# design.net
KiCad netlist of a schematic drawn in Altium Designer
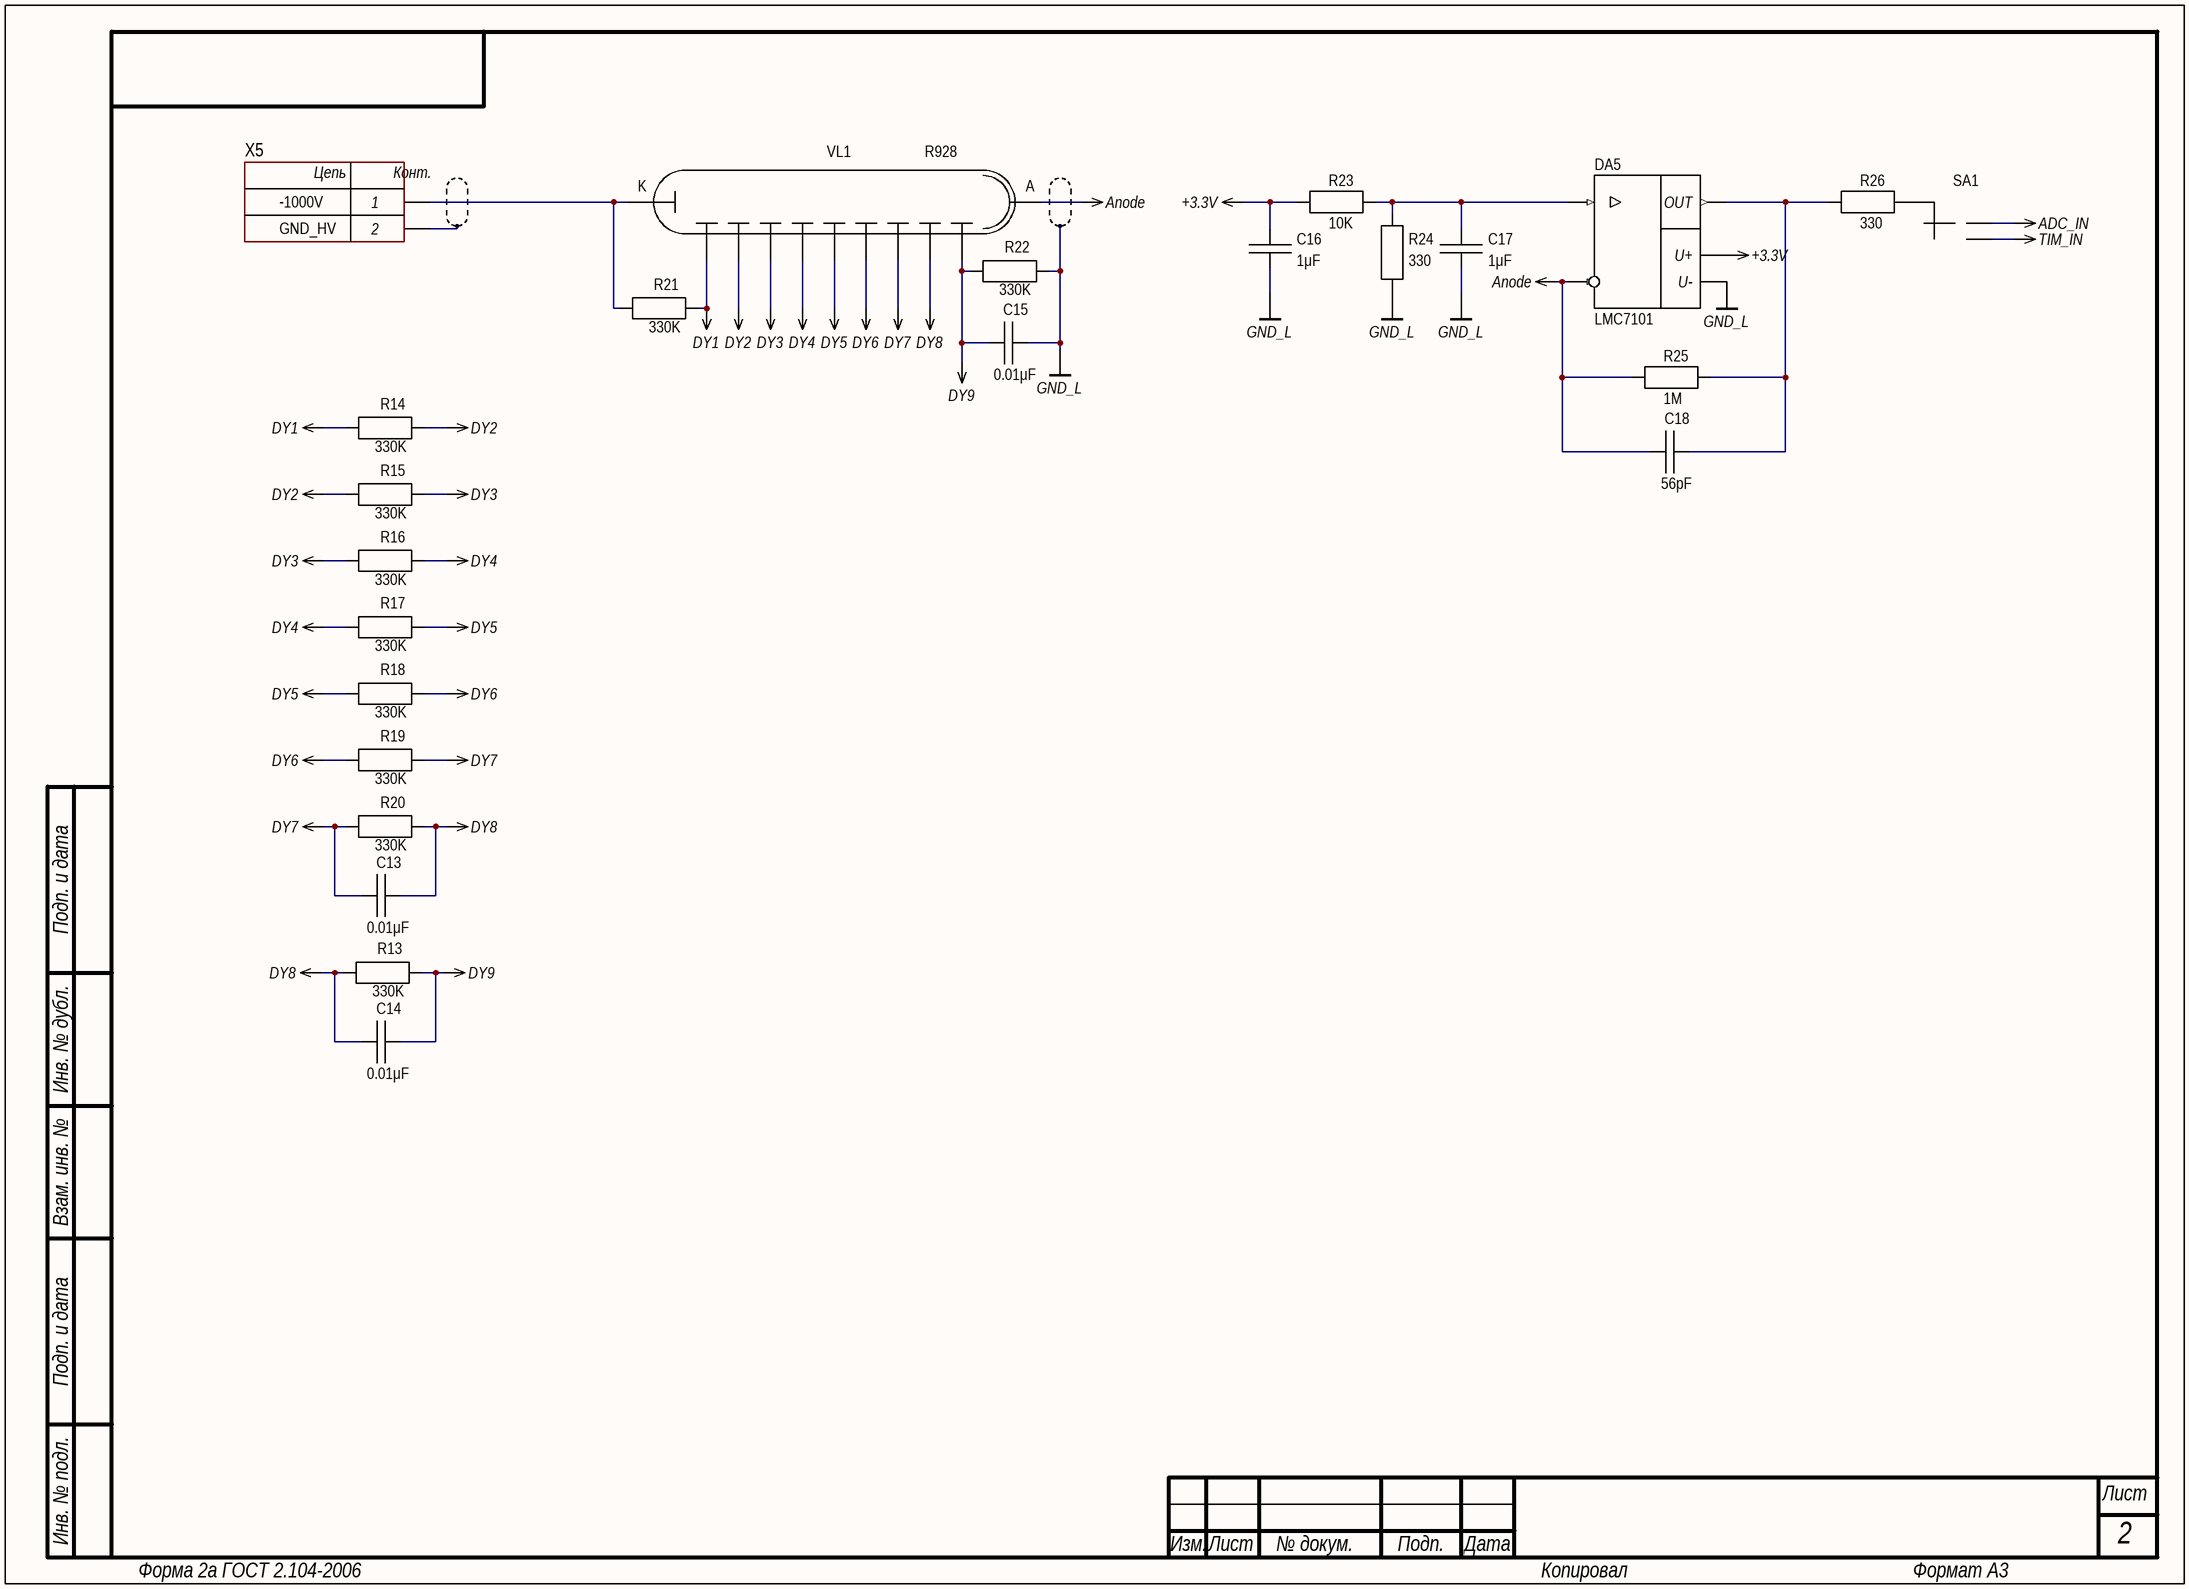
[diagram p0: ФЭУ.SchDoc]

(export (version "E")
  (design (tool "Eeschema 10.0.6"))
  (components
    (comp (ref "C13")
      (value "0.01μF")
      (footprint "CAPASITOR 1206")
      (fields
        (field (name "MANUFACTURER") "Yageo")
        (field (name "PARTNUMBER") "CC1206KRX7R9BB104")
        (field (name "VALUEMANUFACTURERPARTNUMBER") "Ceramic capacitor, 0.01μF, X7R, ±10%, 25V, 1206, -55...+125°C")
      )
      (libsource (lib "MQTT_ESP_lib") (part "CAPASITOR"))
    )
    (comp (ref "C14")
      (value "0.01μF")
      (footprint "CAPASITOR 1206")
      (fields
        (field (name "MANUFACTURER") "Yageo")
        (field (name "PARTNUMBER") "CC1206KRX7R9BB104")
        (field (name "VALUEMANUFACTURERPARTNUMBER") "Ceramic capacitor, 0.01μF, X7R, ±10%, 25V, 1206, -55...+125°C")
      )
      (libsource (lib "MQTT_ESP_lib") (part "CAPASITOR"))
    )
    (comp (ref "C15")
      (value "0.01μF")
      (footprint "CAPASITOR 1206")
      (fields
        (field (name "MANUFACTURER") "Yageo")
        (field (name "PARTNUMBER") "CC1206KRX7R9BB104")
        (field (name "VALUEMANUFACTURERPARTNUMBER") "Ceramic capacitor, 0.01μF, X7R, ±10%, 25V, 1206, -55...+125°C")
      )
      (libsource (lib "MQTT_ESP_lib") (part "CAPASITOR"))
    )
    (comp (ref "C16")
      (value "1μF")
      (footprint "CAPASITOR 1206")
      (fields
        (field (name "MANUFACTURER") "Yageo")
        (field (name "PARTNUMBER") "CC1206KRX7R9BB104")
        (field (name "VALUEMANUFACTURERPARTNUMBER") "Ceramic capacitor, 1μF, X7R, ±10%, 25V, 1206, -55...+125°C")
      )
      (libsource (lib "MQTT_ESP_lib") (part "CAPASITOR"))
    )
    (comp (ref "C17")
      (value "1μF")
      (footprint "CAPASITOR 1206")
      (fields
        (field (name "MANUFACTURER") "Yageo")
        (field (name "PARTNUMBER") "CC1206KRX7R9BB104")
        (field (name "VALUEMANUFACTURERPARTNUMBER") "Ceramic capacitor, 1μF, X7R, ±10%, 25V, 1206, -55...+125°C")
      )
      (libsource (lib "MQTT_ESP_lib") (part "CAPASITOR"))
    )
    (comp (ref "C18")
      (value "56pF")
      (footprint "CAPASITOR 1206")
      (fields
        (field (name "MANUFACTURER") "Yageo")
        (field (name "PARTNUMBER") "CC1206KRX7R9BB104")
        (field (name "VALUEMANUFACTURERPARTNUMBER") "Ceramic capacitor, 56pF, X7R, ±10%, 25V, 1206, -55...+125°C")
      )
      (libsource (lib "MQTT_ESP_lib") (part "CAPASITOR"))
    )
    (comp (ref "DA5")
      (value "Операционный усилитель")
      (libsource (lib "MQTT_ESP_lib") (part "Операционный усилитель"))
    )
    (comp (ref "R13")
      (value "330K")
      (footprint "RESISTOR 1206")
      (fields
        (field (name "MANUFACTURER") "Yageo")
        (field (name "PARTNUMBER") "RC1206JR-07100RL")
        (field (name "VALUEMANUFACTURERPARTNUMBER") "Resistor film, 330K, ±5%, 1206, 0.25W, -55...+125°C")
      )
      (libsource (lib "MQTT_ESP_lib") (part "RESISTOR"))
    )
    (comp (ref "R14")
      (value "330K")
      (footprint "RESISTOR 1206")
      (fields
        (field (name "MANUFACTURER") "Yageo")
        (field (name "PARTNUMBER") "RC1206JR-07100RL")
        (field (name "VALUEMANUFACTURERPARTNUMBER") "Resistor film, 330K, ±5%, 1206, 0.25W, -55...+125°C")
      )
      (libsource (lib "MQTT_ESP_lib") (part "RESISTOR"))
    )
    (comp (ref "R15")
      (value "330K")
      (footprint "RESISTOR 1206")
      (fields
        (field (name "MANUFACTURER") "Yageo")
        (field (name "PARTNUMBER") "RC1206JR-07100RL")
        (field (name "VALUEMANUFACTURERPARTNUMBER") "Resistor film, 330K, ±5%, 1206, 0.25W, -55...+125°C")
      )
      (libsource (lib "MQTT_ESP_lib") (part "RESISTOR"))
    )
    (comp (ref "R16")
      (value "330K")
      (footprint "RESISTOR 1206")
      (fields
        (field (name "MANUFACTURER") "Yageo")
        (field (name "PARTNUMBER") "RC1206JR-07100RL")
        (field (name "VALUEMANUFACTURERPARTNUMBER") "Resistor film, 330K, ±5%, 1206, 0.25W, -55...+125°C")
      )
      (libsource (lib "MQTT_ESP_lib") (part "RESISTOR"))
    )
    (comp (ref "R17")
      (value "330K")
      (footprint "RESISTOR 1206")
      (fields
        (field (name "MANUFACTURER") "Yageo")
        (field (name "PARTNUMBER") "RC1206JR-07100RL")
        (field (name "VALUEMANUFACTURERPARTNUMBER") "Resistor film, 330K, ±5%, 1206, 0.25W, -55...+125°C")
      )
      (libsource (lib "MQTT_ESP_lib") (part "RESISTOR"))
    )
    (comp (ref "R18")
      (value "330K")
      (footprint "RESISTOR 1206")
      (fields
        (field (name "MANUFACTURER") "Yageo")
        (field (name "PARTNUMBER") "RC1206JR-07100RL")
        (field (name "VALUEMANUFACTURERPARTNUMBER") "Resistor film, 330K, ±5%, 1206, 0.25W, -55...+125°C")
      )
      (libsource (lib "MQTT_ESP_lib") (part "RESISTOR"))
    )
    (comp (ref "R19")
      (value "330K")
      (footprint "RESISTOR 1206")
      (fields
        (field (name "MANUFACTURER") "Yageo")
        (field (name "PARTNUMBER") "RC1206JR-07100RL")
        (field (name "VALUEMANUFACTURERPARTNUMBER") "Resistor film, 330K, ±5%, 1206, 0.25W, -55...+125°C")
      )
      (libsource (lib "MQTT_ESP_lib") (part "RESISTOR"))
    )
    (comp (ref "R20")
      (value "330K")
      (footprint "RESISTOR 1206")
      (fields
        (field (name "MANUFACTURER") "Yageo")
        (field (name "PARTNUMBER") "RC1206JR-07100RL")
        (field (name "VALUEMANUFACTURERPARTNUMBER") "Resistor film, 330K, ±5%, 1206, 0.25W, -55...+125°C")
      )
      (libsource (lib "MQTT_ESP_lib") (part "RESISTOR"))
    )
    (comp (ref "R21")
      (value "330K")
      (footprint "RESISTOR 1206")
      (fields
        (field (name "MANUFACTURER") "Yageo")
        (field (name "PARTNUMBER") "RC1206JR-07100RL")
        (field (name "VALUEMANUFACTURERPARTNUMBER") "Resistor film, 330K, ±5%, 1206, 0.25W, -55...+125°C")
      )
      (libsource (lib "MQTT_ESP_lib") (part "RESISTOR"))
    )
    (comp (ref "R22")
      (value "330K")
      (footprint "RESISTOR 1206")
      (fields
        (field (name "MANUFACTURER") "Yageo")
        (field (name "PARTNUMBER") "RC1206JR-07100RL")
        (field (name "VALUEMANUFACTURERPARTNUMBER") "Resistor film, 330K, ±5%, 1206, 0.25W, -55...+125°C")
      )
      (libsource (lib "MQTT_ESP_lib") (part "RESISTOR"))
    )
    (comp (ref "R23")
      (value "10K")
      (footprint "RESISTOR 1206")
      (fields
        (field (name "MANUFACTURER") "Yageo")
        (field (name "PARTNUMBER") "RC1206JR-07100RL")
        (field (name "VALUEMANUFACTURERPARTNUMBER") "Resistor film, 10K, ±5%, 1206, 0.25W, -55...+125°C")
      )
      (libsource (lib "") (part "RESISTOR_2"))
    )
    (comp (ref "R24")
      (value "330")
      (footprint "RESISTOR 1206")
      (fields
        (field (name "MANUFACTURER") "Yageo")
        (field (name "PARTNUMBER") "RC1206JR-07100RL")
        (field (name "VALUEMANUFACTURERPARTNUMBER") "Resistor film, 330, ±5%, 1206, 0.25W, -55...+125°C")
      )
      (libsource (lib "") (part "RESISTOR_1"))
    )
    (comp (ref "R25")
      (value "1M")
      (footprint "RESISTOR 1206")
      (fields
        (field (name "MANUFACTURER") "Yageo")
        (field (name "PARTNUMBER") "RC1206JR-07100RL")
        (field (name "VALUEMANUFACTURERPARTNUMBER") "Resistor film, 1M, ±5%, 1206, 0.25W, -55...+125°C")
      )
      (libsource (lib "MQTT_ESP_lib") (part "RESISTOR"))
    )
    (comp (ref "R26")
      (value "330")
      (footprint "RESISTOR 1206")
      (fields
        (field (name "MANUFACTURER") "Yageo")
        (field (name "PARTNUMBER") "RC1206JR-07100RL")
        (field (name "VALUEMANUFACTURERPARTNUMBER") "Resistor film, 330, ±5%, 1206, 0.25W, -55...+125°C")
      )
      (libsource (lib "MQTT_ESP_lib") (part "RESISTOR"))
    )
    (comp (ref "SA1")
      (value "Двухпозиционный переключатель")
      (libsource (lib "MQTT_ESP_lib") (part "Двухпозиционный переключатель"))
    )
    (comp (ref "VL1") (value "ФЭУ") (libsource (lib "MQTT_ESP_lib") (part "ФЭУ")))
    (comp (ref "X5")
      (value "~")
      (footprint "CON: 6PCV-03-006")
      (fields
        (field (name "MANUFACTURER") "Degson")
        (field (name "VALUEMANUFACTURERPARTNUMBER") "Terminal connector, 2pin, 3.5mm, 300VAC, 10A")
        (field (name "PARTNUMBER") "DG350-3.5-02P-14")
      )
      (libsource (lib "MQTT_ESP_lib") (part "CONNECTOR 2 PIN"))
    )
  )
  (nets
    (net (code "1") (name "+3.3V") (class "Default")
      (node (ref "C16") (pin "1") (pinfunction "1_1") (pintype "passive"))
      (node (ref "DA5") (pin "4") (pinfunction "U+_4") (pintype "passive"))
      (node (ref "R23") (pin "1") (pinfunction "1_1") (pintype "passive"))
    )
    (net (code "2") (name "ADC_IN") (class "Default")
      (node (ref "SA1") (pin "1") (pinfunction "1_1") (pintype "passive"))
    )
    (net (code "3") (name "Anode") (class "Default")
      (node (ref "C18") (pin "1") (pinfunction "1_1") (pintype "passive"))
      (node (ref "DA5") (pin "3") (pinfunction "3_3") (pintype "input"))
      (node (ref "R25") (pin "2") (pinfunction "2_2") (pintype "passive"))
      (node (ref "VL1") (pin "11") (pinfunction "11_11") (pintype "passive"))
    )
    (net (code "4") (name "DY1") (class "Default")
      (node (ref "R14") (pin "2") (pinfunction "2_2") (pintype "passive"))
      (node (ref "R21") (pin "1") (pinfunction "1_1") (pintype "passive"))
      (node (ref "VL1") (pin "2") (pinfunction "2_2") (pintype "passive"))
    )
    (net (code "5") (name "DY2") (class "Default")
      (node (ref "R14") (pin "1") (pinfunction "1_1") (pintype "passive"))
      (node (ref "R15") (pin "2") (pinfunction "2_2") (pintype "passive"))
      (node (ref "VL1") (pin "3") (pinfunction "3_3") (pintype "passive"))
    )
    (net (code "6") (name "DY3") (class "Default")
      (node (ref "R15") (pin "1") (pinfunction "1_1") (pintype "passive"))
      (node (ref "R16") (pin "2") (pinfunction "2_2") (pintype "passive"))
      (node (ref "VL1") (pin "4") (pinfunction "4_4") (pintype "passive"))
    )
    (net (code "7") (name "DY4") (class "Default")
      (node (ref "R16") (pin "1") (pinfunction "1_1") (pintype "passive"))
      (node (ref "R17") (pin "2") (pinfunction "2_2") (pintype "passive"))
      (node (ref "VL1") (pin "5") (pinfunction "5_5") (pintype "passive"))
    )
    (net (code "8") (name "DY5") (class "Default")
      (node (ref "R17") (pin "1") (pinfunction "1_1") (pintype "passive"))
      (node (ref "R18") (pin "2") (pinfunction "2_2") (pintype "passive"))
      (node (ref "VL1") (pin "6") (pinfunction "6_6") (pintype "passive"))
    )
    (net (code "9") (name "DY6") (class "Default")
      (node (ref "R18") (pin "1") (pinfunction "1_1") (pintype "passive"))
      (node (ref "R19") (pin "2") (pinfunction "2_2") (pintype "passive"))
      (node (ref "VL1") (pin "7") (pinfunction "7_7") (pintype "passive"))
    )
    (net (code "10") (name "DY7") (class "Default")
      (node (ref "C13") (pin "2") (pinfunction "2_2") (pintype "passive"))
      (node (ref "R19") (pin "1") (pinfunction "1_1") (pintype "passive"))
      (node (ref "R20") (pin "2") (pinfunction "2_2") (pintype "passive"))
      (node (ref "VL1") (pin "8") (pinfunction "8_8") (pintype "passive"))
    )
    (net (code "11") (name "DY8") (class "Default")
      (node (ref "C13") (pin "1") (pinfunction "1_1") (pintype "passive"))
      (node (ref "C14") (pin "2") (pinfunction "2_2") (pintype "passive"))
      (node (ref "R13") (pin "2") (pinfunction "2_2") (pintype "passive"))
      (node (ref "R20") (pin "1") (pinfunction "1_1") (pintype "passive"))
      (node (ref "VL1") (pin "9") (pinfunction "9_9") (pintype "passive"))
    )
    (net (code "12") (name "DY9") (class "Default")
      (node (ref "C14") (pin "1") (pinfunction "1_1") (pintype "passive"))
      (node (ref "C15") (pin "2") (pinfunction "2_2") (pintype "passive"))
      (node (ref "R13") (pin "1") (pinfunction "1_1") (pintype "passive"))
      (node (ref "R22") (pin "2") (pinfunction "2_2") (pintype "passive"))
      (node (ref "VL1") (pin "10") (pinfunction "10_10") (pintype "passive"))
    )
    (net (code "13") (name "GND_L") (class "Default")
      (node (ref "C15") (pin "1") (pinfunction "1_1") (pintype "passive"))
      (node (ref "C16") (pin "2") (pinfunction "2_2") (pintype "passive"))
      (node (ref "C17") (pin "2") (pinfunction "2_2") (pintype "passive"))
      (node (ref "DA5") (pin "5") (pinfunction "U-_5") (pintype "passive"))
      (node (ref "R22") (pin "1") (pinfunction "1_1") (pintype "passive"))
      (node (ref "R24") (pin "2") (pinfunction "2_2") (pintype "passive"))
    )
    (net (code "14") (name "Net-(C17-Pad1)") (class "Default")
      (node (ref "C17") (pin "1") (pinfunction "1_1") (pintype "passive"))
      (node (ref "DA5") (pin "2") (pinfunction "2_2") (pintype "input"))
      (node (ref "R23") (pin "2") (pinfunction "2_2") (pintype "passive"))
      (node (ref "R24") (pin "1") (pinfunction "1_1") (pintype "passive"))
    )
    (net (code "15") (name "Net-(DA5-OUT)") (class "Default")
      (node (ref "C18") (pin "2") (pinfunction "2_2") (pintype "passive"))
      (node (ref "DA5") (pin "1") (pinfunction "OUT_1") (pintype "output"))
      (node (ref "R25") (pin "1") (pinfunction "1_1") (pintype "passive"))
      (node (ref "R26") (pin "2") (pinfunction "2_2") (pintype "passive"))
    )
    (net (code "16") (name "Net-(R21-Pad2)") (class "Default")
      (node (ref "R21") (pin "2") (pinfunction "2_2") (pintype "passive"))
      (node (ref "VL1") (pin "1") (pinfunction "1_1") (pintype "passive"))
      (node (ref "X5") (pin "1") (pinfunction "1_1") (pintype "passive"))
    )
    (net (code "17") (name "Net-(R26-Pad1)") (class "Default")
      (node (ref "R26") (pin "1") (pinfunction "1_1") (pintype "passive"))
      (node (ref "SA1") (pin "A") (pinfunction "A_A") (pintype "passive"))
    )
    (net (code "18") (name "TIM_IN") (class "Default")
      (node (ref "SA1") (pin "2") (pinfunction "2_2") (pintype "passive"))
    )
    (net (code "19") (name "unconnected-(X5-Pad2)") (class "Default")
      (node (ref "X5") (pin "2") (pinfunction "2_2") (pintype "passive"))
    )
  )
)
